# Schaltplan_SafeScan.net
KiCad netlist of a schematic drawn in EAGLE
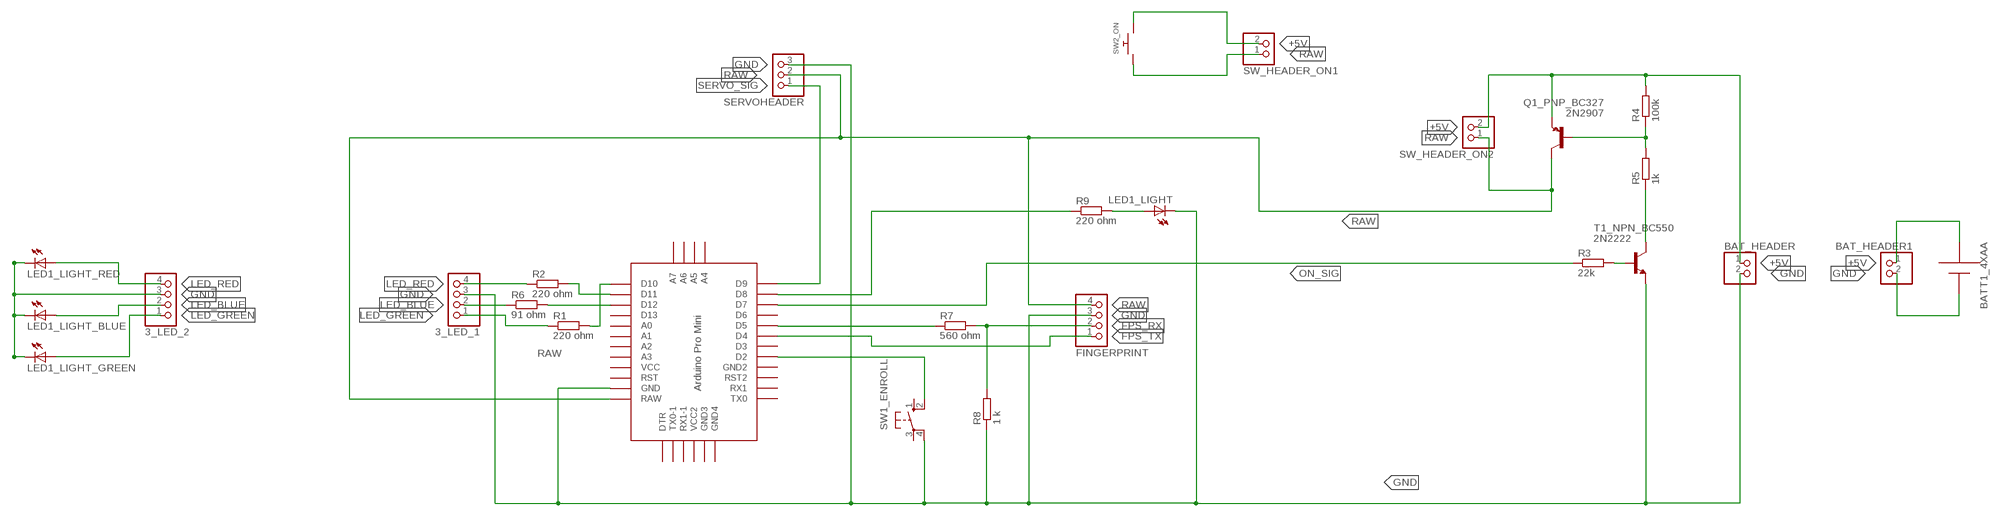
[diagram p0: schematic, sheet 1]

(export (version "E")
  (design (tool "Eeschema 10.0.6"))
  (components
    (comp (ref "3_LED_1")
      (value "PINHD-1X4")
      (footprint "eagle-import:1X04")
      (libsource (lib "eagle-import") (part "PINHD-1X4"))
    )
    (comp (ref "3_LED_2")
      (value "PINHD-1X4")
      (footprint "eagle-import:1X04")
      (libsource (lib "eagle-import") (part "PINHD-1X4"))
    )
    (comp (ref "ARDUINO_PRO_MINI_3.3")
      (value "PRO-MINI")
      (footprint "eagle-import:PRO-MINI")
      (libsource (lib "eagle-import") (part "PRO-MINI"))
    )
    (comp (ref "BATT1_4XAA")
      (value "AAA")
      (footprint "eagle-import:12BH412")
      (libsource (lib "eagle-import") (part "AAA"))
    )
    (comp (ref "BAT_HEADER")
      (value "PINHD-1X2")
      (footprint "eagle-import:1X02")
      (libsource (lib "eagle-import") (part "PINHD-1X2"))
    )
    (comp (ref "BAT_HEADER1")
      (value "PINHD-1X2")
      (footprint "eagle-import:1X02")
      (libsource (lib "eagle-import") (part "PINHD-1X2"))
    )
    (comp (ref "FINGERPRINT")
      (value "PINHD-1X4")
      (footprint "eagle-import:1X04")
      (libsource (lib "eagle-import") (part "PINHD-1X4"))
    )
    (comp (ref "LED1_LIGHT")
      (value "LED5MM")
      (footprint "eagle-import:LED5MM")
      (libsource (lib "eagle-import") (part "LED5MM"))
    )
    (comp (ref "LED1_LIGHT_BLUE")
      (value "LED5MM")
      (footprint "eagle-import:LED5MM")
      (libsource (lib "eagle-import") (part "LED5MM"))
    )
    (comp (ref "LED1_LIGHT_GREEN")
      (value "LED5MM")
      (footprint "eagle-import:LED5MM")
      (libsource (lib "eagle-import") (part "LED5MM"))
    )
    (comp (ref "LED1_LIGHT_RED")
      (value "LED5MM")
      (footprint "eagle-import:LED5MM")
      (libsource (lib "eagle-import") (part "LED5MM"))
    )
    (comp (ref "Q1_PNP_BC327")
      (value "2N2907")
      (footprint "eagle-import:TO92-EBC-OVAL")
      (libsource (lib "eagle-import") (part "2N2907"))
    )
    (comp (ref "R1")
      (value "220 ohm")
      (footprint "eagle-import:0204_5")
      (libsource (lib "eagle-import") (part "R-EU_0204/5"))
    )
    (comp (ref "R2")
      (value "220 ohm")
      (footprint "eagle-import:0204_5")
      (libsource (lib "eagle-import") (part "R-EU_0204/5"))
    )
    (comp (ref "R3")
      (value "22k")
      (footprint "eagle-import:0204_5")
      (libsource (lib "eagle-import") (part "R-EU_0204/5"))
    )
    (comp (ref "R4")
      (value "100k")
      (footprint "eagle-import:0204_5")
      (libsource (lib "eagle-import") (part "R-EU_0204/5"))
    )
    (comp (ref "R5")
      (value "1k")
      (footprint "eagle-import:0204_5")
      (libsource (lib "eagle-import") (part "R-EU_0204/5"))
    )
    (comp (ref "R6")
      (value "91 ohm")
      (footprint "eagle-import:0204_5")
      (libsource (lib "eagle-import") (part "R-EU_0204/5"))
    )
    (comp (ref "R7")
      (value "560 ohm")
      (footprint "eagle-import:0207_15")
      (libsource (lib "eagle-import") (part "R-EU_0207/15"))
    )
    (comp (ref "R8")
      (value "1 k")
      (footprint "eagle-import:0204_5")
      (libsource (lib "eagle-import") (part "R-EU_0204/5"))
    )
    (comp (ref "R9")
      (value "220 ohm")
      (footprint "eagle-import:0204_5")
      (libsource (lib "eagle-import") (part "R-EU_0204/5"))
    )
    (comp (ref "SERVOHEADER")
      (value "PINHD-1X3CB")
      (footprint "eagle-import:1X03-CLEANBIG")
      (libsource (lib "eagle-import") (part "PINHD-1X3CB"))
    )
    (comp (ref "SW1_ENROLL")
      (value "10-XX")
      (footprint "eagle-import:B3F-10XX")
      (fields (field (name "MPN") "B3F-1000"))
      (libsource (lib "eagle-import") (part "10-XX"))
    )
    (comp (ref "SW2_ON")
      (value "SWITCH_PUSHBUTTONEVQ-PE")
      (footprint "eagle-import:TACT_PANA-EVQ")
      (libsource (lib "eagle-import") (part "SWITCH_PUSHBUTTONEVQ-PE"))
    )
    (comp (ref "SW_HEADER_ON1")
      (value "PINHD-1X2")
      (footprint "eagle-import:1X02")
      (libsource (lib "eagle-import") (part "PINHD-1X2"))
    )
    (comp (ref "SW_HEADER_ON2")
      (value "PINHD-1X2")
      (footprint "eagle-import:1X02")
      (libsource (lib "eagle-import") (part "PINHD-1X2"))
    )
    (comp (ref "T1_NPN_BC550")
      (value "2N2222")
      (footprint "eagle-import:TO92-EBC-OVAL")
      (libsource (lib "eagle-import") (part "2N2222"))
    )
  )
  (nets
    (net (code "1") (name "+5V") (class "Default")
      (node (ref "BATT1_4XAA") (pin "-") (pinfunction "-_-") (pintype "bidirectional"))
      (node (ref "BAT_HEADER") (pin "1") (pinfunction "1_1") (pintype "passive"))
      (node (ref "BAT_HEADER1") (pin "1") (pinfunction "1_1") (pintype "passive"))
      (node (ref "Q1_PNP_BC327") (pin "E") (pinfunction "E_E") (pintype "passive"))
      (node (ref "R4") (pin "2") (pinfunction "2_2") (pintype "passive"))
      (node (ref "SW2_ON") (pin "P$2") (pinfunction "P$2_P$2") (pintype "passive"))
      (node (ref "SW_HEADER_ON1") (pin "2") (pinfunction "2_2") (pintype "passive"))
      (node (ref "SW_HEADER_ON2") (pin "2") (pinfunction "2_2") (pintype "passive"))
    )
    (net (code "2") (name "FPS_RX") (class "Default")
      (node (ref "FINGERPRINT") (pin "2") (pinfunction "2_2") (pintype "passive"))
      (node (ref "R7") (pin "2") (pinfunction "2_2") (pintype "passive"))
      (node (ref "R8") (pin "2") (pinfunction "2_2") (pintype "passive"))
    )
    (net (code "3") (name "FPS_TX") (class "Default")
      (node (ref "ARDUINO_PRO_MINI_3.3") (pin "D4") (pinfunction "D4_D4") (pintype "bidirectional"))
      (node (ref "FINGERPRINT") (pin "1") (pinfunction "1_1") (pintype "passive"))
    )
    (net (code "4") (name "GND") (class "Default")
      (node (ref "3_LED_1") (pin "3") (pinfunction "3_3") (pintype "passive"))
      (node (ref "3_LED_2") (pin "3") (pinfunction "3_3") (pintype "passive"))
      (node (ref "ARDUINO_PRO_MINI_3.3") (pin "GND") (pinfunction "GND_GND") (pintype "input"))
      (node (ref "BATT1_4XAA") (pin "+") (pinfunction "+_+") (pintype "bidirectional"))
      (node (ref "BAT_HEADER") (pin "2") (pinfunction "2_2") (pintype "passive"))
      (node (ref "BAT_HEADER1") (pin "2") (pinfunction "2_2") (pintype "passive"))
      (node (ref "FINGERPRINT") (pin "3") (pinfunction "3_3") (pintype "passive"))
      (node (ref "LED1_LIGHT") (pin "K") (pinfunction "C_K") (pintype "passive"))
      (node (ref "LED1_LIGHT_BLUE") (pin "K") (pinfunction "C_K") (pintype "passive"))
      (node (ref "LED1_LIGHT_GREEN") (pin "K") (pinfunction "C_K") (pintype "passive"))
      (node (ref "LED1_LIGHT_RED") (pin "K") (pinfunction "C_K") (pintype "passive"))
      (node (ref "R8") (pin "1") (pinfunction "1_1") (pintype "passive"))
      (node (ref "SERVOHEADER") (pin "3") (pinfunction "3_3") (pintype "passive"))
      (node (ref "SW1_ENROLL") (pin "4") (pinfunction "P1_4") (pintype "passive"))
      (node (ref "T1_NPN_BC550") (pin "E") (pinfunction "E_E") (pintype "passive"))
    )
    (net (code "5") (name "LED_BLUE") (class "Default")
      (node (ref "3_LED_1") (pin "2") (pinfunction "2_2") (pintype "passive"))
      (node (ref "3_LED_2") (pin "2") (pinfunction "2_2") (pintype "passive"))
      (node (ref "LED1_LIGHT_BLUE") (pin "A") (pinfunction "A_A") (pintype "passive"))
      (node (ref "R6") (pin "1") (pinfunction "1_1") (pintype "passive"))
    )
    (net (code "6") (name "LED_GREEN") (class "Default")
      (node (ref "3_LED_1") (pin "1") (pinfunction "1_1") (pintype "passive"))
      (node (ref "3_LED_2") (pin "1") (pinfunction "1_1") (pintype "passive"))
      (node (ref "LED1_LIGHT_GREEN") (pin "A") (pinfunction "A_A") (pintype "passive"))
      (node (ref "R1") (pin "1") (pinfunction "1_1") (pintype "passive"))
    )
    (net (code "7") (name "LED_RED") (class "Default")
      (node (ref "3_LED_1") (pin "4") (pinfunction "4_4") (pintype "passive"))
      (node (ref "3_LED_2") (pin "4") (pinfunction "4_4") (pintype "passive"))
      (node (ref "LED1_LIGHT_RED") (pin "A") (pinfunction "A_A") (pintype "passive"))
      (node (ref "R2") (pin "1") (pinfunction "1_1") (pintype "passive"))
    )
    (net (code "8") (name "Net-(ARDUINO_PRO_MINI_3.3-PadD5)") (class "Default")
      (node (ref "ARDUINO_PRO_MINI_3.3") (pin "D5") (pinfunction "D5_D5") (pintype "bidirectional"))
      (node (ref "R7") (pin "1") (pinfunction "1_1") (pintype "passive"))
    )
    (net (code "9") (name "Net-(ARDUINO_PRO_MINI_3.3-PadD8)") (class "Default")
      (node (ref "ARDUINO_PRO_MINI_3.3") (pin "D8") (pinfunction "D8_D8") (pintype "bidirectional"))
      (node (ref "R9") (pin "1") (pinfunction "1_1") (pintype "passive"))
    )
    (net (code "10") (name "Net-(ARDUINO_PRO_MINI_3.3-PadD10)") (class "Default")
      (node (ref "ARDUINO_PRO_MINI_3.3") (pin "D10") (pinfunction "D10_D10") (pintype "bidirectional"))
      (node (ref "R1") (pin "2") (pinfunction "2_2") (pintype "passive"))
    )
    (net (code "11") (name "Net-(ARDUINO_PRO_MINI_3.3-PadD11)") (class "Default")
      (node (ref "ARDUINO_PRO_MINI_3.3") (pin "D11") (pinfunction "D11_D11") (pintype "bidirectional"))
      (node (ref "R2") (pin "2") (pinfunction "2_2") (pintype "passive"))
    )
    (net (code "12") (name "Net-(ARDUINO_PRO_MINI_3.3-PadD12)") (class "Default")
      (node (ref "ARDUINO_PRO_MINI_3.3") (pin "D12") (pinfunction "D12_D12") (pintype "bidirectional"))
      (node (ref "R6") (pin "2") (pinfunction "2_2") (pintype "passive"))
    )
    (net (code "13") (name "Net-(LED1_LIGHT-PadA)") (class "Default")
      (node (ref "LED1_LIGHT") (pin "A") (pinfunction "A_A") (pintype "passive"))
      (node (ref "R9") (pin "2") (pinfunction "2_2") (pintype "passive"))
    )
    (net (code "14") (name "Net-(Q1_PNP_BC327-PadB)") (class "Default")
      (node (ref "Q1_PNP_BC327") (pin "B") (pinfunction "B_B") (pintype "passive"))
      (node (ref "R4") (pin "1") (pinfunction "1_1") (pintype "passive"))
      (node (ref "R5") (pin "2") (pinfunction "2_2") (pintype "passive"))
    )
    (net (code "15") (name "Net-(R3-Pad2)") (class "Default")
      (node (ref "R3") (pin "2") (pinfunction "2_2") (pintype "passive"))
      (node (ref "T1_NPN_BC550") (pin "B") (pinfunction "B_B") (pintype "passive"))
    )
    (net (code "16") (name "Net-(R5-Pad1)") (class "Default")
      (node (ref "R5") (pin "1") (pinfunction "1_1") (pintype "passive"))
      (node (ref "T1_NPN_BC550") (pin "C") (pinfunction "C_C") (pintype "passive"))
    )
    (net (code "17") (name "Net-(SW1_ENROLL-S1)") (class "Default")
      (node (ref "ARDUINO_PRO_MINI_3.3") (pin "D2") (pinfunction "D2_D2") (pintype "bidirectional"))
      (node (ref "SW1_ENROLL") (pin "2") (pinfunction "S1_2") (pintype "passive"))
    )
    (net (code "18") (name "ON_SIG") (class "Default")
      (node (ref "ARDUINO_PRO_MINI_3.3") (pin "D7") (pinfunction "D7_D7") (pintype "bidirectional"))
      (node (ref "R3") (pin "1") (pinfunction "1_1") (pintype "passive"))
    )
    (net (code "19") (name "RAW") (class "Default")
      (node (ref "ARDUINO_PRO_MINI_3.3") (pin "RAW") (pinfunction "RAW_RAW") (pintype "power_in"))
      (node (ref "FINGERPRINT") (pin "4") (pinfunction "4_4") (pintype "passive"))
      (node (ref "Q1_PNP_BC327") (pin "C") (pinfunction "C_C") (pintype "passive"))
      (node (ref "SERVOHEADER") (pin "2") (pinfunction "2_2") (pintype "passive"))
      (node (ref "SW2_ON") (pin "P$1") (pinfunction "P$1_P$1") (pintype "passive"))
      (node (ref "SW_HEADER_ON1") (pin "1") (pinfunction "1_1") (pintype "passive"))
      (node (ref "SW_HEADER_ON2") (pin "1") (pinfunction "1_1") (pintype "passive"))
    )
    (net (code "20") (name "SERVO_SIG") (class "Default")
      (node (ref "ARDUINO_PRO_MINI_3.3") (pin "D9") (pinfunction "D9_D9") (pintype "bidirectional"))
      (node (ref "SERVOHEADER") (pin "1") (pinfunction "1_1") (pintype "passive"))
    )
    (net (code "21") (name "unconnected-(ARDUINO_PRO_MINI_3.3-GND2-PadGND1)") (class "Default")
      (node (ref "ARDUINO_PRO_MINI_3.3") (pin "GND1") (pinfunction "GND2_GND1") (pintype "bidirectional"))
    )
    (net (code "22") (name "unconnected-(ARDUINO_PRO_MINI_3.3-GND4-PadGND2)") (class "Default")
      (node (ref "ARDUINO_PRO_MINI_3.3") (pin "GND2") (pinfunction "GND4_GND2") (pintype "bidirectional"))
    )
    (net (code "23") (name "unconnected-(ARDUINO_PRO_MINI_3.3-PadA0)") (class "Default")
      (node (ref "ARDUINO_PRO_MINI_3.3") (pin "A0") (pinfunction "A0_A0") (pintype "bidirectional"))
    )
    (net (code "24") (name "unconnected-(ARDUINO_PRO_MINI_3.3-PadA1)") (class "Default")
      (node (ref "ARDUINO_PRO_MINI_3.3") (pin "A1") (pinfunction "A1_A1") (pintype "bidirectional"))
    )
    (net (code "25") (name "unconnected-(ARDUINO_PRO_MINI_3.3-PadA2)") (class "Default")
      (node (ref "ARDUINO_PRO_MINI_3.3") (pin "A2") (pinfunction "A2_A2") (pintype "bidirectional"))
    )
    (net (code "26") (name "unconnected-(ARDUINO_PRO_MINI_3.3-PadA3)") (class "Default")
      (node (ref "ARDUINO_PRO_MINI_3.3") (pin "A3") (pinfunction "A3_A3") (pintype "bidirectional"))
    )
    (net (code "27") (name "unconnected-(ARDUINO_PRO_MINI_3.3-PadA4)") (class "Default")
      (node (ref "ARDUINO_PRO_MINI_3.3") (pin "A4") (pinfunction "A4_A4") (pintype "bidirectional"))
    )
    (net (code "28") (name "unconnected-(ARDUINO_PRO_MINI_3.3-PadA5)") (class "Default")
      (node (ref "ARDUINO_PRO_MINI_3.3") (pin "A5") (pinfunction "A5_A5") (pintype "bidirectional"))
    )
    (net (code "29") (name "unconnected-(ARDUINO_PRO_MINI_3.3-PadA6)") (class "Default")
      (node (ref "ARDUINO_PRO_MINI_3.3") (pin "A6") (pinfunction "A6_A6") (pintype "bidirectional"))
    )
    (net (code "30") (name "unconnected-(ARDUINO_PRO_MINI_3.3-PadA7)") (class "Default")
      (node (ref "ARDUINO_PRO_MINI_3.3") (pin "A7") (pinfunction "A7_A7") (pintype "bidirectional"))
    )
    (net (code "31") (name "unconnected-(ARDUINO_PRO_MINI_3.3-PadD3)") (class "Default")
      (node (ref "ARDUINO_PRO_MINI_3.3") (pin "D3") (pinfunction "D3_D3") (pintype "bidirectional"))
    )
    (net (code "32") (name "unconnected-(ARDUINO_PRO_MINI_3.3-PadD6)") (class "Default")
      (node (ref "ARDUINO_PRO_MINI_3.3") (pin "D6") (pinfunction "D6_D6") (pintype "bidirectional"))
    )
    (net (code "33") (name "unconnected-(ARDUINO_PRO_MINI_3.3-PadD13)") (class "Default")
      (node (ref "ARDUINO_PRO_MINI_3.3") (pin "D13") (pinfunction "D13_D13") (pintype "bidirectional"))
    )
    (net (code "34") (name "unconnected-(ARDUINO_PRO_MINI_3.3-PadDTR)") (class "Default")
      (node (ref "ARDUINO_PRO_MINI_3.3") (pin "DTR") (pinfunction "DTR_DTR") (pintype "bidirectional"))
    )
    (net (code "35") (name "unconnected-(ARDUINO_PRO_MINI_3.3-PadGND3)") (class "Default")
      (node (ref "ARDUINO_PRO_MINI_3.3") (pin "GND3") (pinfunction "GND3_GND3") (pintype "bidirectional"))
    )
    (net (code "36") (name "unconnected-(ARDUINO_PRO_MINI_3.3-PadRST)") (class "Default")
      (node (ref "ARDUINO_PRO_MINI_3.3") (pin "RST") (pinfunction "RST_RST") (pintype "bidirectional"))
    )
    (net (code "37") (name "unconnected-(ARDUINO_PRO_MINI_3.3-PadRX1)") (class "Default")
      (node (ref "ARDUINO_PRO_MINI_3.3") (pin "RX1") (pinfunction "RX1_RX1") (pintype "bidirectional"))
    )
    (net (code "38") (name "unconnected-(ARDUINO_PRO_MINI_3.3-PadRX1-1)") (class "Default")
      (node (ref "ARDUINO_PRO_MINI_3.3") (pin "RX1-1") (pinfunction "RX1-1_RX1-1") (pintype "bidirectional"))
    )
    (net (code "39") (name "unconnected-(ARDUINO_PRO_MINI_3.3-PadTX0)") (class "Default")
      (node (ref "ARDUINO_PRO_MINI_3.3") (pin "TX0") (pinfunction "TX0_TX0") (pintype "bidirectional"))
    )
    (net (code "40") (name "unconnected-(ARDUINO_PRO_MINI_3.3-PadTX0-1)") (class "Default")
      (node (ref "ARDUINO_PRO_MINI_3.3") (pin "TX0-1") (pinfunction "TX0-1_TX0-1") (pintype "bidirectional"))
    )
    (net (code "41") (name "unconnected-(ARDUINO_PRO_MINI_3.3-PadVCC)") (class "Default")
      (node (ref "ARDUINO_PRO_MINI_3.3") (pin "VCC") (pinfunction "VCC_VCC") (pintype "bidirectional"))
    )
    (net (code "42") (name "unconnected-(ARDUINO_PRO_MINI_3.3-RST2-PadRST1)") (class "Default")
      (node (ref "ARDUINO_PRO_MINI_3.3") (pin "RST1") (pinfunction "RST2_RST1") (pintype "bidirectional"))
    )
    (net (code "43") (name "unconnected-(ARDUINO_PRO_MINI_3.3-VCC2-PadVCC1)") (class "Default")
      (node (ref "ARDUINO_PRO_MINI_3.3") (pin "VCC1") (pinfunction "VCC2_VCC1") (pintype "bidirectional"))
    )
    (net (code "44") (name "unconnected-(SW1_ENROLL-P-Pad3)") (class "Default")
      (node (ref "SW1_ENROLL") (pin "3") (pinfunction "P_3") (pintype "passive"))
    )
    (net (code "45") (name "unconnected-(SW1_ENROLL-S-Pad1)") (class "Default")
      (node (ref "SW1_ENROLL") (pin "1") (pinfunction "S_1") (pintype "passive"))
    )
  )
)
